# WIFI.net
KiCad netlist of a schematic drawn in Altium Designer
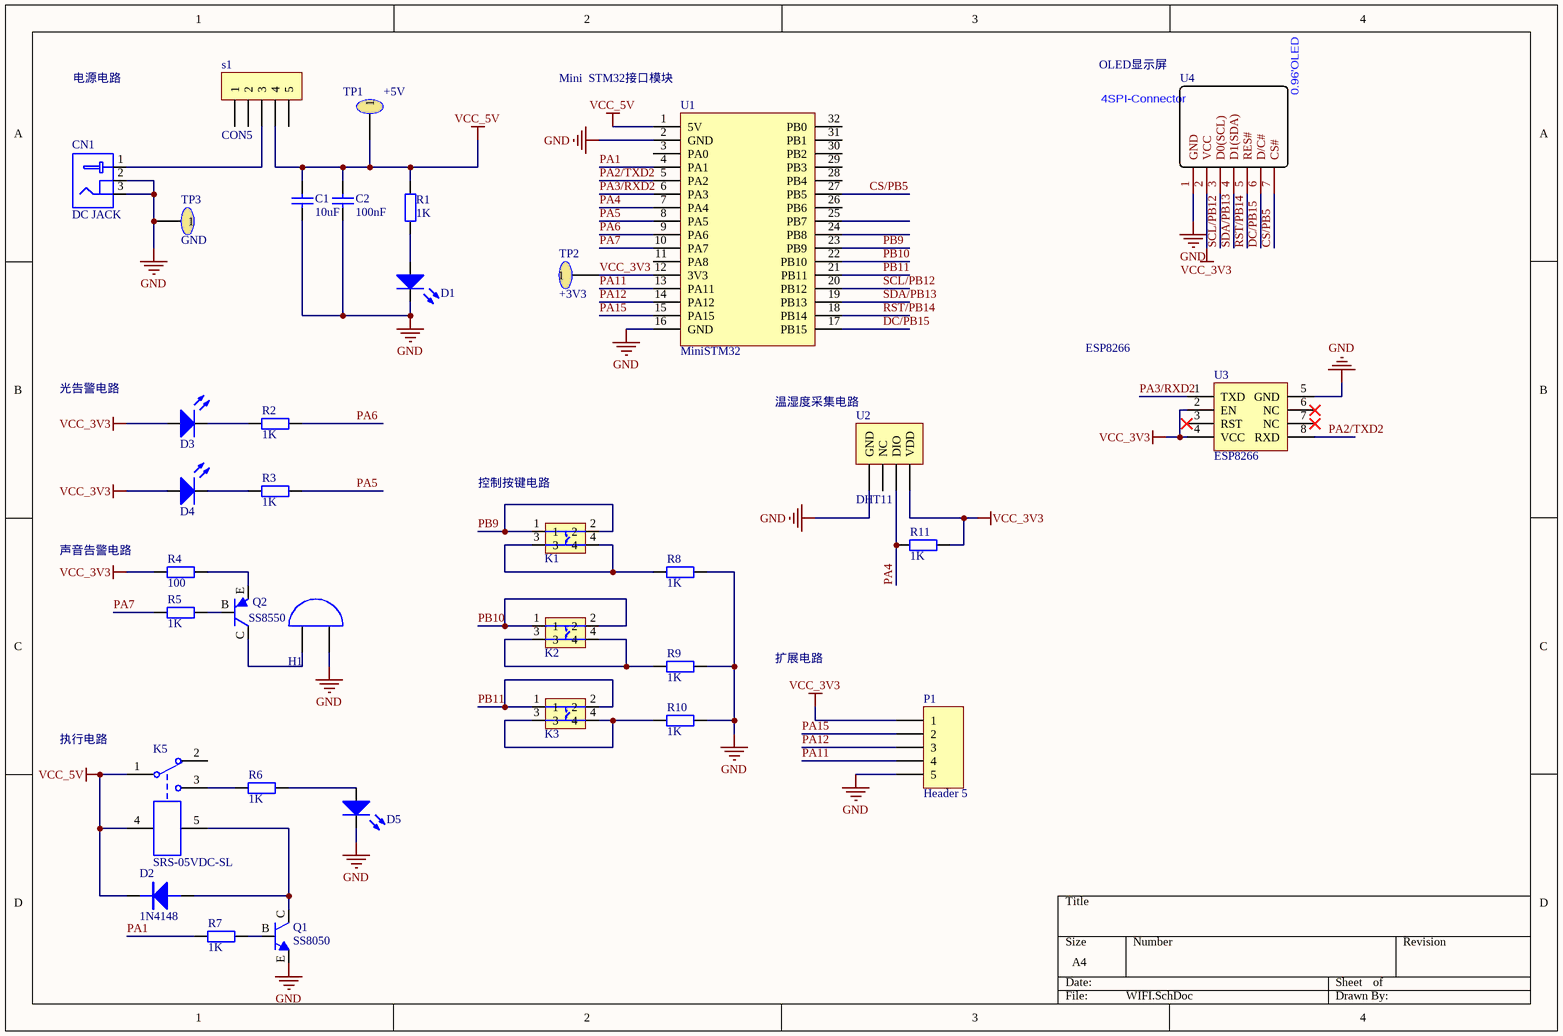
[diagram p0: WIFI.SchDoc]

(export (version "E")
  (design (tool "Eeschema 10.0.6"))
  (components
    (comp (ref "C1")
      (value "10uF")
      (footprint "0805贴片电容")
      (description "100nF,0805,±10%")
      (libsource (lib "基于WiFi的温湿度测量与传输系统原理图库") (part "0805贴片电容"))
    )
    (comp (ref "C2")
      (value "100nF")
      (footprint "0805贴片电容")
      (description "100nF,0805,±10%")
      (libsource (lib "基于WiFi的温湿度测量与传输系统原理图库") (part "0805贴片电容"))
    )
    (comp (ref "CN1")
      (value "DC JACK")
      (footprint "DC JACK")
      (description "DC JACK电源插座,5.5mm孔径,3脚接插件")
      (libsource (lib "基于WiFi的温湿度测量与传输系统原理图库") (part "DC JACK"))
    )
    (comp (ref "D1")
      (value "0805 LED")
      (footprint "0805 LED")
      (description "发光二极管,绿光,0805")
      (libsource (lib "基于WiFi的温湿度测量与传输系统原理图库") (part "0805 LED"))
    )
    (comp (ref "D2")
      (value "1N4148")
      (footprint "LL34圆柱")
      (description "1N4148圆柱形")
      (libsource (lib "基于WiFi的温湿度测量与传输系统原理图库") (part "1N4148圆柱"))
    )
    (comp (ref "D3")
      (value "0805 LED")
      (footprint "0805 LED")
      (description "发光二极管,绿光,0805")
      (libsource (lib "基于WiFi的温湿度测量与传输系统原理图库") (part "0805 LED"))
    )
    (comp (ref "D4")
      (value "0805 LED")
      (footprint "0805 LED")
      (description "发光二极管,绿光,0805")
      (libsource (lib "基于WiFi的温湿度测量与传输系统原理图库") (part "0805 LED"))
    )
    (comp (ref "D5")
      (value "0805 LED")
      (footprint "0805 LED")
      (description "发光二极管,绿光,0805")
      (libsource (lib "基于WiFi的温湿度测量与传输系统原理图库") (part "0805 LED"))
    )
    (comp (ref "H1")
      (value "蜂鸣器")
      (footprint "buzzer")
      (description "TMB-12-A05,电磁式,2脚直插,直径12mm,脚间距6.8mm")
      (libsource (lib "基于WiFi的温湿度测量与传输系统原理图库") (part "BELL"))
    )
    (comp (ref "K1")
      (value "SW6X6轻触开关_1")
      (footprint "SW6X6轻触开关")
      (description "6*6mm*4.5mm轻触开关,4脚插件,180°")
      (libsource (lib "基于WiFi的温湿度测量与传输系统原理图库") (part "SW6X6轻触开关_1"))
    )
    (comp (ref "K2")
      (value "SW6X6轻触开关_1")
      (footprint "SW6X6轻触开关")
      (description "6*6mm*4.5mm轻触开关,4脚插件,180°")
      (libsource (lib "基于WiFi的温湿度测量与传输系统原理图库") (part "SW6X6轻触开关_1"))
    )
    (comp (ref "K3")
      (value "SW6X6轻触开关_1")
      (footprint "SW6X6轻触开关")
      (description "6*6mm*4.5mm轻触开关,4脚插件,180°")
      (libsource (lib "基于WiFi的温湿度测量与传输系统原理图库") (part "SW6X6轻触开关_1"))
    )
    (comp (ref "K5")
      (value "SRS-05VDC-SL")
      (footprint "继电器")
      (description "SRS-05VDC-SL,6脚插件,单刀双掷")
      (libsource (lib "基于WiFi的温湿度测量与传输系统原理图库") (part "继电器"))
    )
    (comp (ref "P1")
      (value "Header 5")
      (footprint "HDR1X5")
      (description "Header, 5-Pin")
      (fields (field (name "PUBLISHER") "Altium Limited"))
      (libsource (lib "基于WiFi的温湿度测量与传输系统原理图库") (part "Header 5"))
    )
    (comp (ref "Q1")
      (value "SS8050")
      (footprint "插件三极管TO-92")
      (description "SS8050,直插NPN三极管,TO-92封装")
      (libsource (lib "基于WiFi的温湿度测量与传输系统原理图库") (part "插件NPN三极管"))
    )
    (comp (ref "Q2")
      (value "SS8550")
      (footprint "插件三极管TO-92")
      (description "SS8550,直插PNP三极管,TO-92封装")
      (libsource (lib "基于WiFi的温湿度测量与传输系统原理图库") (part "插件PNP三极管"))
    )
    (comp (ref "R1")
      (value "1K")
      (footprint "0805贴片电阻")
      (description "1KΩ,0805,±5%")
      (libsource (lib "") (part "0805贴片电阻_1"))
    )
    (comp (ref "R2")
      (value "1K")
      (footprint "0805贴片电阻")
      (description "1KΩ,0805,±5%")
      (libsource (lib "基于WiFi的温湿度测量与传输系统原理图库") (part "0805贴片电阻"))
    )
    (comp (ref "R3")
      (value "1K")
      (footprint "0805贴片电阻")
      (description "1KΩ,0805,±5%")
      (libsource (lib "基于WiFi的温湿度测量与传输系统原理图库") (part "0805贴片电阻"))
    )
    (comp (ref "R4")
      (value "100")
      (footprint "0805贴片电阻")
      (description "1KΩ,0805,±5%")
      (libsource (lib "基于WiFi的温湿度测量与传输系统原理图库") (part "0805贴片电阻"))
    )
    (comp (ref "R5")
      (value "1K")
      (footprint "0805贴片电阻")
      (description "1KΩ,0805,±5%")
      (libsource (lib "基于WiFi的温湿度测量与传输系统原理图库") (part "0805贴片电阻"))
    )
    (comp (ref "R6")
      (value "1K")
      (footprint "0805贴片电阻")
      (description "1KΩ,0805,±5%")
      (libsource (lib "基于WiFi的温湿度测量与传输系统原理图库") (part "0805贴片电阻"))
    )
    (comp (ref "R7")
      (value "1K")
      (footprint "0805贴片电阻")
      (description "1KΩ,0805,±5%")
      (libsource (lib "基于WiFi的温湿度测量与传输系统原理图库") (part "0805贴片电阻"))
    )
    (comp (ref "R8")
      (value "1K")
      (footprint "0805贴片电阻")
      (description "1KΩ,0805,±5%")
      (libsource (lib "基于WiFi的温湿度测量与传输系统原理图库") (part "0805贴片电阻"))
    )
    (comp (ref "R9")
      (value "1K")
      (footprint "0805贴片电阻")
      (description "1KΩ,0805,±5%")
      (libsource (lib "基于WiFi的温湿度测量与传输系统原理图库") (part "0805贴片电阻"))
    )
    (comp (ref "R10")
      (value "1K")
      (footprint "0805贴片电阻")
      (description "1KΩ,0805,±5%")
      (libsource (lib "基于WiFi的温湿度测量与传输系统原理图库") (part "0805贴片电阻"))
    )
    (comp (ref "R11")
      (value "1K")
      (footprint "0805贴片电阻")
      (description "1KΩ,0805,±5%")
      (libsource (lib "基于WiFi的温湿度测量与传输系统原理图库") (part "0805贴片电阻"))
    )
    (comp (ref "s1")
      (value "CON5")
      (footprint "拨动开关5脚")
      (description "12*6mm,SS12F44G5 #KG44,5-pin,3mm间距,滑竿高度10mm,单刀双掷开关")
      (libsource (lib "基于WiFi的温湿度测量与传输系统原理图库") (part "拨动开关5脚"))
    )
    (comp (ref "TP1")
      (value "+5V")
      (footprint "单过孔（有外框）")
      (libsource (lib "基于WiFi的温湿度测量与传输系统原理图库") (part "测试点"))
    )
    (comp (ref "TP2")
      (value "+3V3")
      (footprint "单过孔（有外框）")
      (libsource (lib "基于WiFi的温湿度测量与传输系统原理图库") (part "测试点"))
    )
    (comp (ref "TP3")
      (value "GND")
      (footprint "单过孔（有外框）")
      (libsource (lib "基于WiFi的温湿度测量与传输系统原理图库") (part "测试点"))
    )
    (comp (ref "U1")
      (value "MiniSTM32")
      (footprint "Mini STM32(19.5mm)")
      (libsource (lib "基于WiFi的温湿度测量与传输系统原理图库") (part "MiniSTM32（19.5mm）"))
    )
    (comp (ref "U2")
      (value "DHT11")
      (footprint "DHT11（卧倒）")
      (libsource (lib "基于WiFi的温湿度测量与传输系统原理图库") (part "DHT11"))
    )
    (comp (ref "U3")
      (value "ESP8266")
      (footprint "ESP8266(有边框)")
      (description "双排直插座,2*4-pin,2.54mm间距,180°")
      (libsource (lib "基于WiFi的温湿度测量与传输系统原理图库") (part "ESP8266"))
    )
    (comp (ref "U4")
      (value "0.96寸OLED(7脚)")
      (footprint "0.96寸OLED7脚")
      (description "单排直插座,1*7-pin,2.54mm间距,180°")
      (libsource (lib "基于WiFi的温湿度测量与传输系统原理图库") (part "0.96寸OLED(7脚)"))
    )
  )
  (nets
    (net (code "1") (name "/CS{slash}PB5") (class "Default")
      (node (ref "U1") (pin "27") (pinfunction "PB5_27") (pintype "passive"))
      (node (ref "U4") (pin "7") (pinfunction "CS#_7") (pintype "passive"))
    )
    (net (code "2") (name "/DC{slash}PB15") (class "Default")
      (node (ref "U1") (pin "17") (pinfunction "PB15_17") (pintype "passive"))
      (node (ref "U4") (pin "6") (pinfunction "D/C#_6") (pintype "passive"))
    )
    (net (code "3") (name "/PA1") (class "Default")
      (node (ref "R7") (pin "1") (pinfunction "1_1") (pintype "passive"))
      (node (ref "U1") (pin "4") (pinfunction "PA1_4") (pintype "passive"))
    )
    (net (code "4") (name "/PA2{slash}TXD2") (class "Default")
      (node (ref "U1") (pin "5") (pinfunction "PA2_5") (pintype "passive"))
      (node (ref "U3") (pin "8") (pinfunction "RXD_8") (pintype "passive"))
    )
    (net (code "5") (name "/PA3{slash}RXD2") (class "Default")
      (node (ref "U1") (pin "6") (pinfunction "PA3_6") (pintype "passive"))
      (node (ref "U3") (pin "1") (pinfunction "TXD_1") (pintype "passive"))
    )
    (net (code "6") (name "/PA4") (class "Default")
      (node (ref "R11") (pin "1") (pinfunction "1_1") (pintype "passive"))
      (node (ref "U1") (pin "7") (pinfunction "PA4_7") (pintype "passive"))
      (node (ref "U2") (pin "2") (pinfunction "DIO_2") (pintype "passive"))
    )
    (net (code "7") (name "/PA5") (class "Default")
      (node (ref "R3") (pin "2") (pinfunction "2_2") (pintype "passive"))
      (node (ref "U1") (pin "8") (pinfunction "PA5_8") (pintype "passive"))
    )
    (net (code "8") (name "/PA6") (class "Default")
      (node (ref "R2") (pin "2") (pinfunction "2_2") (pintype "passive"))
      (node (ref "U1") (pin "9") (pinfunction "PA6_9") (pintype "passive"))
    )
    (net (code "9") (name "/PA7") (class "Default")
      (node (ref "R5") (pin "1") (pinfunction "1_1") (pintype "passive"))
      (node (ref "U1") (pin "10") (pinfunction "PA7_10") (pintype "passive"))
    )
    (net (code "10") (name "/PA11") (class "Default")
      (node (ref "P1") (pin "4") (pinfunction "4_4") (pintype "passive"))
      (node (ref "U1") (pin "13") (pinfunction "PA11_13") (pintype "passive"))
    )
    (net (code "11") (name "/PA12") (class "Default")
      (node (ref "P1") (pin "3") (pinfunction "3_3") (pintype "passive"))
      (node (ref "U1") (pin "14") (pinfunction "PA12_14") (pintype "passive"))
    )
    (net (code "12") (name "/PA15") (class "Default")
      (node (ref "P1") (pin "2") (pinfunction "2_2") (pintype "passive"))
      (node (ref "U1") (pin "15") (pinfunction "PA15_15") (pintype "passive"))
    )
    (net (code "13") (name "/PB9") (class "Default")
      (node (ref "K1") (pin "1") (pinfunction "1_1") (pintype "passive"))
      (node (ref "K1") (pin "2") (pinfunction "2_2") (pintype "passive"))
      (node (ref "U1") (pin "23") (pinfunction "PB9_23") (pintype "passive"))
    )
    (net (code "14") (name "/PB10") (class "Default")
      (node (ref "K2") (pin "1") (pinfunction "1_1") (pintype "passive"))
      (node (ref "K2") (pin "2") (pinfunction "2_2") (pintype "passive"))
      (node (ref "U1") (pin "22") (pinfunction "PB10_22") (pintype "passive"))
    )
    (net (code "15") (name "/PB11") (class "Default")
      (node (ref "K3") (pin "1") (pinfunction "1_1") (pintype "passive"))
      (node (ref "K3") (pin "2") (pinfunction "2_2") (pintype "passive"))
      (node (ref "U1") (pin "21") (pinfunction "PB11_21") (pintype "passive"))
    )
    (net (code "16") (name "/RST{slash}PB14") (class "Default")
      (node (ref "U1") (pin "18") (pinfunction "PB14_18") (pintype "passive"))
      (node (ref "U4") (pin "5") (pinfunction "RES#_5") (pintype "passive"))
    )
    (net (code "17") (name "/SCL{slash}PB12") (class "Default")
      (node (ref "U1") (pin "20") (pinfunction "PB12_20") (pintype "passive"))
      (node (ref "U4") (pin "3") (pinfunction "D0(SCL)_3") (pintype "passive"))
    )
    (net (code "18") (name "/SDA{slash}PB13") (class "Default")
      (node (ref "U1") (pin "19") (pinfunction "PB13_19") (pintype "passive"))
      (node (ref "U4") (pin "4") (pinfunction "D1(SDA)_4") (pintype "passive"))
    )
    (net (code "19") (name "GND") (class "Default")
      (node (ref "C1") (pin "1") (pinfunction "1_1") (pintype "passive"))
      (node (ref "C2") (pin "1") (pinfunction "1_1") (pintype "passive"))
      (node (ref "CN1") (pin "2") (pintype "passive"))
      (node (ref "CN1") (pin "3") (pintype "passive"))
      (node (ref "D1") (pin "2") (pinfunction "K_2") (pintype "passive"))
      (node (ref "D5") (pin "2") (pinfunction "K_2") (pintype "passive"))
      (node (ref "H1") (pin "2") (pinfunction "2_2") (pintype "passive"))
      (node (ref "P1") (pin "5") (pinfunction "5_5") (pintype "passive"))
      (node (ref "Q1") (pin "E") (pinfunction "E_E") (pintype "passive"))
      (node (ref "R10") (pin "2") (pinfunction "2_2") (pintype "passive"))
      (node (ref "R8") (pin "2") (pinfunction "2_2") (pintype "passive"))
      (node (ref "R9") (pin "2") (pinfunction "2_2") (pintype "passive"))
      (node (ref "TP3") (pin "1") (pinfunction "1_1") (pintype "passive"))
      (node (ref "U1") (pin "16") (pinfunction "GND_16") (pintype "passive"))
      (node (ref "U1") (pin "2") (pinfunction "GND_2") (pintype "passive"))
      (node (ref "U2") (pin "4") (pinfunction "GND_4") (pintype "passive"))
      (node (ref "U3") (pin "5") (pinfunction "GND_5") (pintype "passive"))
      (node (ref "U4") (pin "1") (pinfunction "GND_1") (pintype "passive"))
    )
    (net (code "20") (name "Net-(CN1-Pad1)") (class "Default")
      (node (ref "CN1") (pin "1") (pintype "passive"))
      (node (ref "s1") (pin "3") (pinfunction "3_3") (pintype "passive"))
    )
    (net (code "21") (name "Net-(D1-A)") (class "Default")
      (node (ref "D1") (pin "1") (pinfunction "A_1") (pintype "passive"))
      (node (ref "R1") (pin "1") (pinfunction "1_1") (pintype "passive"))
    )
    (net (code "22") (name "Net-(D2-A)") (class "Default")
      (node (ref "D2") (pin "1") (pinfunction "A_1") (pintype "passive"))
      (node (ref "K5") (pin "5") (pinfunction "5_5") (pintype "passive"))
      (node (ref "Q1") (pin "C") (pinfunction "C_C") (pintype "passive"))
    )
    (net (code "23") (name "Net-(D3-K)") (class "Default")
      (node (ref "D3") (pin "2") (pinfunction "K_2") (pintype "passive"))
      (node (ref "R2") (pin "1") (pinfunction "1_1") (pintype "passive"))
    )
    (net (code "24") (name "Net-(D4-K)") (class "Default")
      (node (ref "D4") (pin "2") (pinfunction "K_2") (pintype "passive"))
      (node (ref "R3") (pin "1") (pinfunction "1_1") (pintype "passive"))
    )
    (net (code "25") (name "Net-(D5-A)") (class "Default")
      (node (ref "D5") (pin "1") (pinfunction "A_1") (pintype "passive"))
      (node (ref "R6") (pin "2") (pinfunction "2_2") (pintype "passive"))
    )
    (net (code "26") (name "Net-(H1-Pad1)") (class "Default")
      (node (ref "H1") (pin "1") (pinfunction "1_1") (pintype "passive"))
      (node (ref "Q2") (pin "C") (pinfunction "C_C") (pintype "passive"))
    )
    (net (code "27") (name "Net-(K1-Pad3)") (class "Default")
      (node (ref "K1") (pin "3") (pinfunction "3_3") (pintype "passive"))
      (node (ref "K1") (pin "4") (pinfunction "4_4") (pintype "passive"))
      (node (ref "R8") (pin "1") (pinfunction "1_1") (pintype "passive"))
    )
    (net (code "28") (name "Net-(K2-Pad3)") (class "Default")
      (node (ref "K2") (pin "3") (pinfunction "3_3") (pintype "passive"))
      (node (ref "K2") (pin "4") (pinfunction "4_4") (pintype "passive"))
      (node (ref "R9") (pin "1") (pinfunction "1_1") (pintype "passive"))
    )
    (net (code "29") (name "Net-(K3-Pad3)") (class "Default")
      (node (ref "K3") (pin "3") (pinfunction "3_3") (pintype "passive"))
      (node (ref "K3") (pin "4") (pinfunction "4_4") (pintype "passive"))
      (node (ref "R10") (pin "1") (pinfunction "1_1") (pintype "passive"))
    )
    (net (code "30") (name "Net-(K5-Pad3)") (class "Default")
      (node (ref "K5") (pin "3") (pinfunction "3_3") (pintype "passive"))
      (node (ref "R6") (pin "1") (pinfunction "1_1") (pintype "passive"))
    )
    (net (code "31") (name "Net-(Q1-PadB)") (class "Default")
      (node (ref "Q1") (pin "B") (pinfunction "B_B") (pintype "passive"))
      (node (ref "R7") (pin "2") (pinfunction "2_2") (pintype "passive"))
    )
    (net (code "32") (name "Net-(Q2-PadB)") (class "Default")
      (node (ref "Q2") (pin "B") (pinfunction "B_B") (pintype "passive"))
      (node (ref "R5") (pin "2") (pinfunction "2_2") (pintype "passive"))
    )
    (net (code "33") (name "Net-(Q2-PadE)") (class "Default")
      (node (ref "Q2") (pin "E") (pinfunction "E_E") (pintype "passive"))
      (node (ref "R4") (pin "2") (pinfunction "2_2") (pintype "passive"))
    )
    (net (code "34") (name "VCC_3V3") (class "Default")
      (node (ref "D3") (pin "1") (pinfunction "A_1") (pintype "passive"))
      (node (ref "D4") (pin "1") (pinfunction "A_1") (pintype "passive"))
      (node (ref "P1") (pin "1") (pinfunction "1_1") (pintype "passive"))
      (node (ref "R11") (pin "2") (pinfunction "2_2") (pintype "passive"))
      (node (ref "R4") (pin "1") (pinfunction "1_1") (pintype "passive"))
      (node (ref "TP2") (pin "1") (pinfunction "1_1") (pintype "passive"))
      (node (ref "U1") (pin "12") (pinfunction "3V3_12") (pintype "passive"))
      (node (ref "U2") (pin "1") (pinfunction "VDD_1") (pintype "passive"))
      (node (ref "U3") (pin "2") (pinfunction "EN_2") (pintype "passive"))
      (node (ref "U3") (pin "4") (pinfunction "VCC_4") (pintype "passive"))
      (node (ref "U4") (pin "2") (pinfunction "VCC_2") (pintype "passive"))
    )
    (net (code "35") (name "VCC_5V") (class "Default")
      (node (ref "C1") (pin "2") (pinfunction "2_2") (pintype "passive"))
      (node (ref "C2") (pin "2") (pinfunction "2_2") (pintype "passive"))
      (node (ref "D2") (pin "2") (pinfunction "K_2") (pintype "passive"))
      (node (ref "K5") (pin "1") (pinfunction "1_1") (pintype "passive"))
      (node (ref "K5") (pin "4") (pinfunction "4_4") (pintype "passive"))
      (node (ref "R1") (pin "2") (pinfunction "2_2") (pintype "passive"))
      (node (ref "TP1") (pin "1") (pinfunction "1_1") (pintype "passive"))
      (node (ref "U1") (pin "1") (pinfunction "5V_1") (pintype "passive"))
      (node (ref "s1") (pin "4") (pinfunction "4_4") (pintype "passive"))
    )
    (net (code "36") (name "unconnected-(K5-Pad2)") (class "Default")
      (node (ref "K5") (pin "2") (pinfunction "2_2") (pintype "passive"))
    )
    (net (code "37") (name "unconnected-(U1-PA0-Pad3)") (class "Default")
      (node (ref "U1") (pin "3") (pinfunction "PA0_3") (pintype "passive"))
    )
    (net (code "38") (name "unconnected-(U1-PA8-Pad11)") (class "Default")
      (node (ref "U1") (pin "11") (pinfunction "PA8_11") (pintype "passive"))
    )
    (net (code "39") (name "unconnected-(U1-PB0-Pad32)") (class "Default")
      (node (ref "U1") (pin "32") (pinfunction "PB0_32") (pintype "passive"))
    )
    (net (code "40") (name "unconnected-(U1-PB1-Pad31)") (class "Default")
      (node (ref "U1") (pin "31") (pinfunction "PB1_31") (pintype "passive"))
    )
    (net (code "41") (name "unconnected-(U1-PB2-Pad30)") (class "Default")
      (node (ref "U1") (pin "30") (pinfunction "PB2_30") (pintype "passive"))
    )
    (net (code "42") (name "unconnected-(U1-PB3-Pad29)") (class "Default")
      (node (ref "U1") (pin "29") (pinfunction "PB3_29") (pintype "passive"))
    )
    (net (code "43") (name "unconnected-(U1-PB4-Pad28)") (class "Default")
      (node (ref "U1") (pin "28") (pinfunction "PB4_28") (pintype "passive"))
    )
    (net (code "44") (name "unconnected-(U1-PB6-Pad26)") (class "Default")
      (node (ref "U1") (pin "26") (pinfunction "PB6_26") (pintype "passive"))
    )
    (net (code "45") (name "unconnected-(U1-PB7-Pad25)") (class "Default")
      (node (ref "U1") (pin "25") (pinfunction "PB7_25") (pintype "passive"))
    )
    (net (code "46") (name "unconnected-(U1-PB8-Pad24)") (class "Default")
      (node (ref "U1") (pin "24") (pinfunction "PB8_24") (pintype "passive"))
    )
    (net (code "47") (name "unconnected-(U2-NC-Pad3)") (class "Default")
      (node (ref "U2") (pin "3") (pinfunction "NC_3") (pintype "passive"))
    )
    (net (code "48") (name "unconnected-(U3-NC-Pad6)") (class "Default")
      (node (ref "U3") (pin "6") (pinfunction "NC_6") (pintype "passive+no_connect"))
    )
    (net (code "49") (name "unconnected-(U3-NC-Pad7)") (class "Default")
      (node (ref "U3") (pin "7") (pinfunction "NC_7") (pintype "passive+no_connect"))
    )
    (net (code "50") (name "unconnected-(U3-RST-Pad3)") (class "Default")
      (node (ref "U3") (pin "3") (pinfunction "RST_3") (pintype "passive+no_connect"))
    )
    (net (code "51") (name "unconnected-(s1-Pad1)") (class "Default")
      (node (ref "s1") (pin "1") (pinfunction "1_1") (pintype "passive"))
    )
    (net (code "52") (name "unconnected-(s1-Pad2)") (class "Default")
      (node (ref "s1") (pin "2") (pinfunction "2_2") (pintype "passive"))
    )
    (net (code "53") (name "unconnected-(s1-Pad5)") (class "Default")
      (node (ref "s1") (pin "5") (pinfunction "5_5") (pintype "passive"))
    )
  )
)
